# relay_isolator_1A.net
KiCad netlist of a schematic drawn in EAGLE
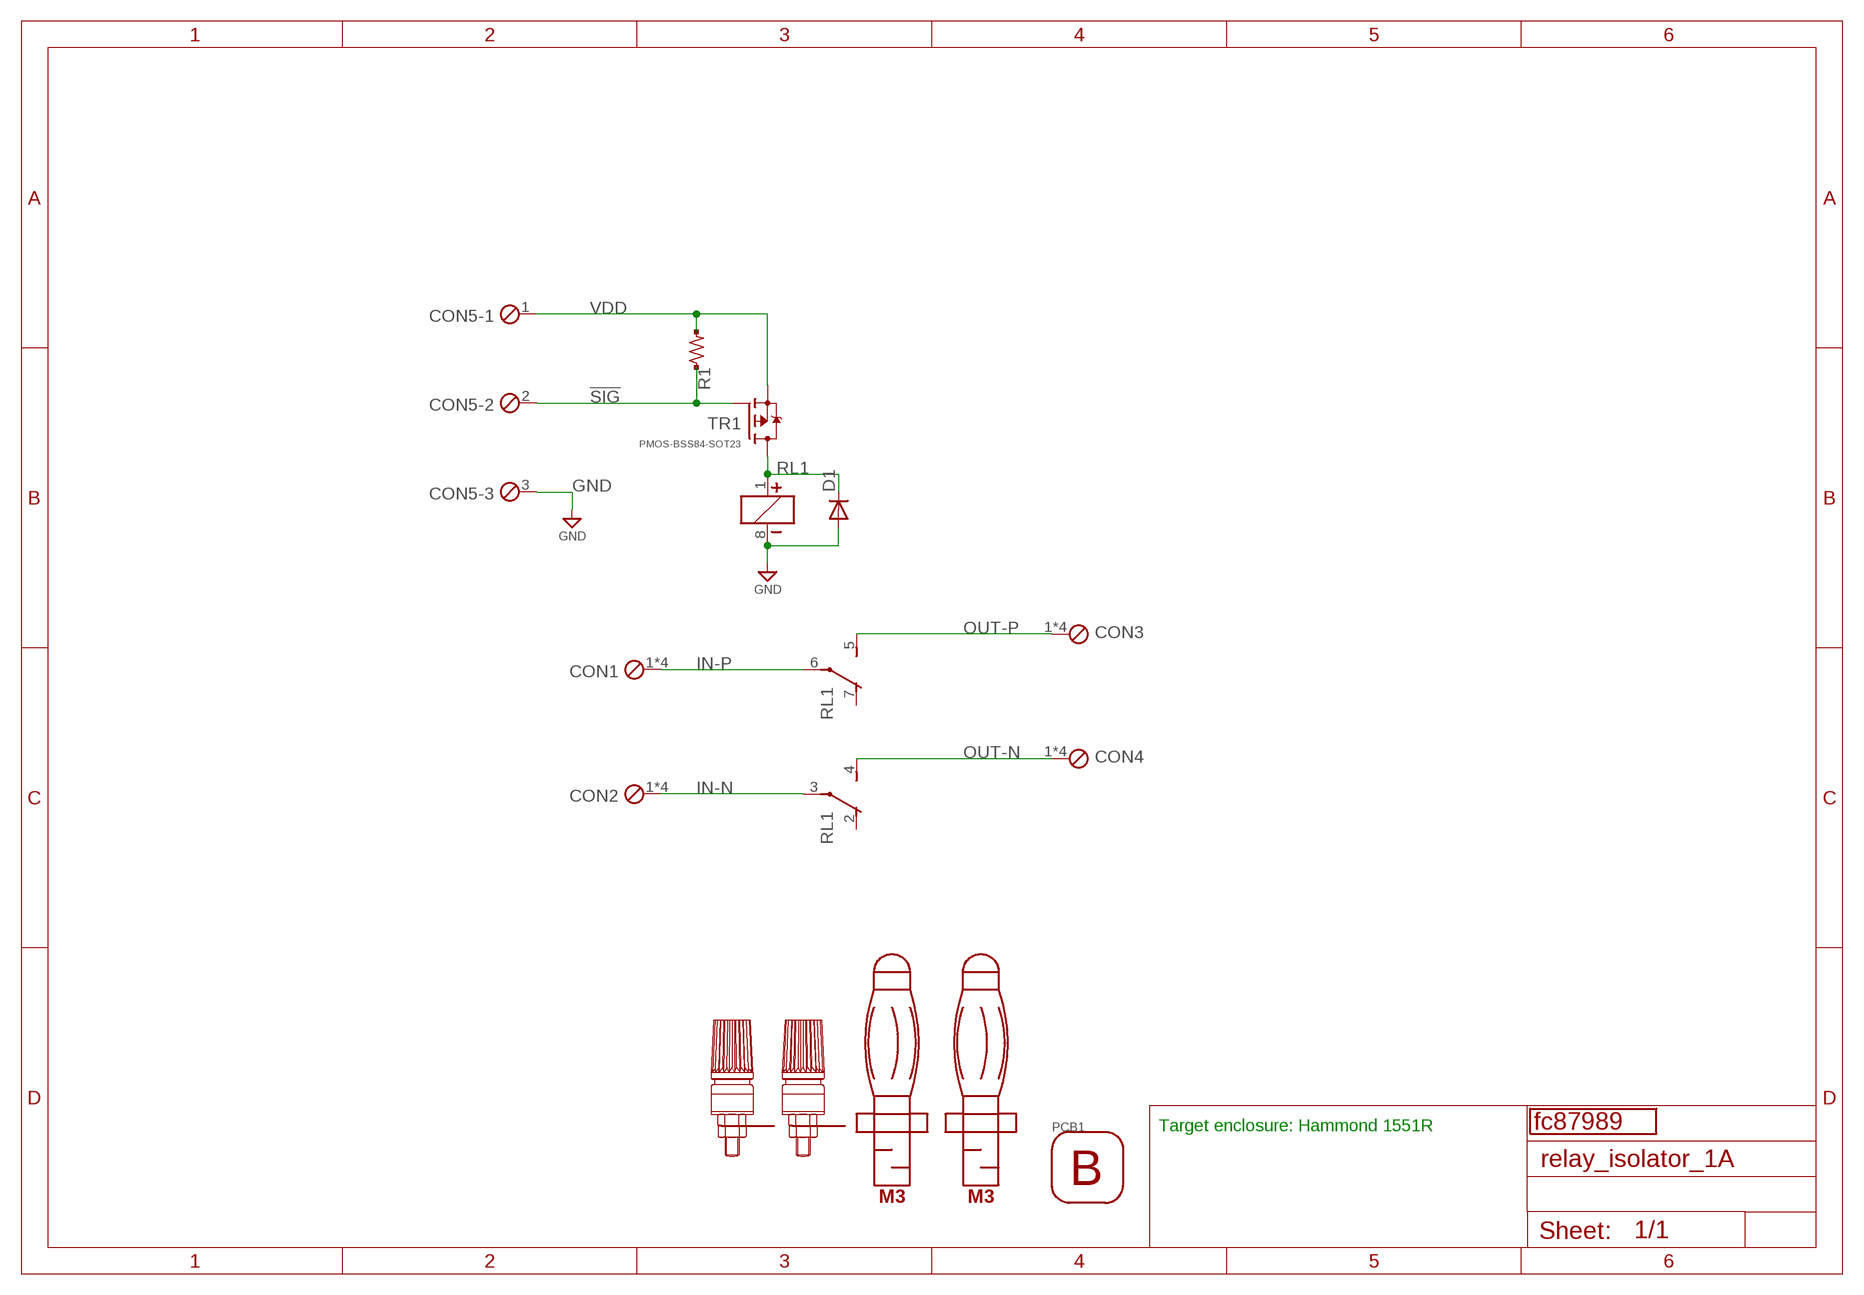
[diagram p0: schematic, sheet 1]

(export (version "E")
  (design (tool "Eeschema 10.0.6"))
  (components
    (comp (ref "CON1")
      (value "KEYSTONE-7790")
      (footprint "eagle-import:KEYSTONE7790")
      (libsource (lib "eagle-import") (part "KEYSTONE-7790"))
    )
    (comp (ref "CON2")
      (value "KEYSTONE-7790")
      (footprint "eagle-import:KEYSTONE7790")
      (libsource (lib "eagle-import") (part "KEYSTONE-7790"))
    )
    (comp (ref "CON3")
      (value "KEYSTONE-7792")
      (footprint "eagle-import:KEYSTONE7790")
      (libsource (lib "eagle-import") (part "KEYSTONE-7792"))
    )
    (comp (ref "CON4")
      (value "KEYSTONE-7792")
      (footprint "eagle-import:KEYSTONE7790")
      (libsource (lib "eagle-import") (part "KEYSTONE-7792"))
    )
    (comp (ref "CON5")
      (value "ETB43034B")
      (footprint "eagle-import:ETB43034")
      (libsource (lib "eagle-import") (part "ETB43034B"))
    )
    (comp (ref "D1")
      (value "DIODE2-100V0.3A-SOD123")
      (footprint "eagle-import:DIODE-2125")
      (libsource (lib "eagle-import") (part "DIODE2--SOD123100V0.3A"))
    )
    (comp (ref "GIT1")
      (value "fc87989")
      (footprint "eagle-import:GIT-REVISION_1.7")
      (libsource (lib "eagle-import") (part "GIT-REVISION_1.7"))
    )
    (comp (ref "PCB1")
      (value "HAMMOND-PCB-BK-1551R")
      (footprint "eagle-import:HAMMOND-1551R")
      (libsource (lib "eagle-import") (part "HAMMOND-PCB--1551RBK"))
    )
    (comp (ref "R1")
      (value "R-US-10K-1608")
      (footprint "eagle-import:R-1608-PADPAD")
      (libsource (lib "eagle-import") (part "R-US--160810K"))
    )
    (comp (ref "REF1")
      (value "POMONA72918")
      (footprint "eagle-import:POMONA72918")
      (libsource (lib "eagle-import") (part "POMONA72918"))
    )
    (comp (ref "REF2")
      (value "POMONA72918")
      (footprint "eagle-import:POMONA72918")
      (libsource (lib "eagle-import") (part "POMONA72918"))
    )
    (comp (ref "REF3")
      (value "T-6530")
      (footprint "eagle-import:T-6530")
      (libsource (lib "eagle-import") (part "T-6530"))
    )
    (comp (ref "REF4")
      (value "T-6530")
      (footprint "eagle-import:T-6530")
      (libsource (lib "eagle-import") (part "T-6530"))
    )
    (comp (ref "RL1")
      (value "RELAY-2C-POL-5V-G6K-2P")
      (footprint "eagle-import:G6K-2P")
      (libsource (lib "eagle-import") (part "RELAY-2C-POL--G6K-2P5V"))
    )
    (comp (ref "TR1")
      (value "PMOS-BSS84-SOT23")
      (footprint "eagle-import:SOT95P300X140-3N")
      (libsource (lib "eagle-import") (part "PMOS--SOT23BSS84"))
    )
  )
  (nets
    (net (code "1") (name "/IN-N") (class "Default")
      (node (ref "CON2") (pin "1") (pinfunction "1_1") (pintype "passive"))
      (node (ref "CON2") (pin "2") (pinfunction "1_2") (pintype "passive"))
      (node (ref "CON2") (pin "3") (pinfunction "1_3") (pintype "passive"))
      (node (ref "CON2") (pin "4") (pinfunction "1_4") (pintype "passive"))
      (node (ref "RL1") (pin "3") (pinfunction "COM_3") (pintype "passive"))
    )
    (net (code "2") (name "/IN-P") (class "Default")
      (node (ref "CON1") (pin "1") (pinfunction "1_1") (pintype "passive"))
      (node (ref "CON1") (pin "2") (pinfunction "1_2") (pintype "passive"))
      (node (ref "CON1") (pin "3") (pinfunction "1_3") (pintype "passive"))
      (node (ref "CON1") (pin "4") (pinfunction "1_4") (pintype "passive"))
      (node (ref "RL1") (pin "6") (pinfunction "COM_6") (pintype "passive"))
    )
    (net (code "3") (name "/OUT-N") (class "Default")
      (node (ref "CON4") (pin "1") (pinfunction "1_1") (pintype "passive"))
      (node (ref "CON4") (pin "2") (pinfunction "1_2") (pintype "passive"))
      (node (ref "CON4") (pin "3") (pinfunction "1_3") (pintype "passive"))
      (node (ref "CON4") (pin "4") (pinfunction "1_4") (pintype "passive"))
      (node (ref "RL1") (pin "4") (pinfunction "NO_4") (pintype "passive"))
    )
    (net (code "4") (name "/OUT-P") (class "Default")
      (node (ref "CON3") (pin "1") (pinfunction "1_1") (pintype "passive"))
      (node (ref "CON3") (pin "2") (pinfunction "1_2") (pintype "passive"))
      (node (ref "CON3") (pin "3") (pinfunction "1_3") (pintype "passive"))
      (node (ref "CON3") (pin "4") (pinfunction "1_4") (pintype "passive"))
      (node (ref "RL1") (pin "5") (pinfunction "NO_5") (pintype "passive"))
    )
    (net (code "5") (name "/VDD") (class "Default")
      (node (ref "CON5") (pin "1") (pinfunction "1_1") (pintype "passive"))
      (node (ref "R1") (pin "2") (pinfunction "2_2") (pintype "passive"))
      (node (ref "TR1") (pin "2") (pinfunction "S_2") (pintype "passive"))
    )
    (net (code "6") (name "/~{SIG}") (class "Default")
      (node (ref "CON5") (pin "2") (pinfunction "1_2") (pintype "passive"))
      (node (ref "R1") (pin "1") (pinfunction "1_1") (pintype "passive"))
      (node (ref "TR1") (pin "1") (pinfunction "G_1") (pintype "passive"))
    )
    (net (code "7") (name "GND") (class "Default")
      (node (ref "CON5") (pin "3") (pinfunction "1_3") (pintype "passive"))
      (node (ref "D1") (pin "A") (pinfunction "A_A") (pintype "passive"))
      (node (ref "RL1") (pin "8") (pinfunction "2_8") (pintype "passive"))
    )
    (net (code "8") (name "Net-(D1-C)") (class "Default")
      (node (ref "D1") (pin "K") (pinfunction "C_K") (pintype "passive"))
      (node (ref "RL1") (pin "1") (pinfunction "1_1") (pintype "passive"))
      (node (ref "TR1") (pin "3") (pinfunction "D_3") (pintype "passive"))
    )
    (net (code "9") (name "unconnected-(RL1B-NC-Pad7)") (class "Default")
      (node (ref "RL1") (pin "7") (pinfunction "NC_7") (pintype "passive"))
    )
    (net (code "10") (name "unconnected-(RL1C-NC-Pad2)") (class "Default")
      (node (ref "RL1") (pin "2") (pinfunction "NC_2") (pintype "passive"))
    )
  )
)
